# bbf-europower.net
KiCad netlist of a schematic drawn in EAGLE
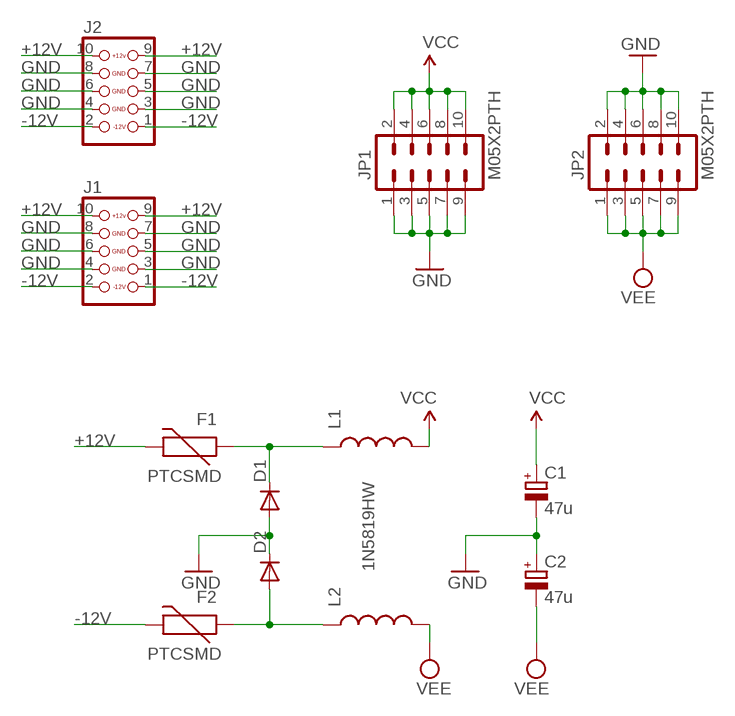
[diagram p0: schematic, sheet 1]

(export (version "E")
  (design (tool "Eeschema 10.0.6"))
  (components
    (comp (ref "C1")
      (value "47u")
      (footprint "eagle-import:E2-5")
      (libsource (lib "eagle-import") (part "CPOL-EUE2-5"))
    )
    (comp (ref "C2")
      (value "47u")
      (footprint "eagle-import:E2-5")
      (libsource (lib "eagle-import") (part "CPOL-EUE2-5"))
    )
    (comp (ref "D1")
      (value "1N5819HW")
      (footprint "eagle-import:SOD123")
      (libsource (lib "eagle-import") (part "DIODE-SOD123"))
    )
    (comp (ref "D2")
      (value "1N5819HW")
      (footprint "eagle-import:SOD123")
      (libsource (lib "eagle-import") (part "DIODE-SOD123"))
    )
    (comp (ref "F1")
      (value "PTCSMD")
      (footprint "eagle-import:PTC-1206")
      (libsource (lib "eagle-import") (part "PTCSMD"))
    )
    (comp (ref "F2")
      (value "PTCSMD")
      (footprint "eagle-import:PTC-1206")
      (libsource (lib "eagle-import") (part "PTCSMD"))
    )
    (comp (ref "J1")
      (value "CON_HEADER_2X05-PTH")
      (footprint "eagle-import:M2X5")
      (libsource (lib "eagle-import") (part "CON_HEADER_2X05-PTH"))
    )
    (comp (ref "J2")
      (value "CON_HEADER_2X05-PTH")
      (footprint "eagle-import:M2X5")
      (libsource (lib "eagle-import") (part "CON_HEADER_2X05-PTH"))
    )
    (comp (ref "JP1")
      (value "M05X2PTH")
      (footprint "eagle-import:AVR_ICSP")
      (libsource (lib "eagle-import") (part "M05X2PTH"))
    )
    (comp (ref "JP2")
      (value "M05X2PTH")
      (footprint "eagle-import:AVR_ICSP")
      (libsource (lib "eagle-import") (part "M05X2PTH"))
    )
    (comp (ref "L1")
      (value "INDUCTOR0603")
      (footprint "eagle-import:0603")
      (libsource (lib "eagle-import") (part "INDUCTOR0603"))
    )
    (comp (ref "L2")
      (value "INDUCTOR0603")
      (footprint "eagle-import:0603")
      (libsource (lib "eagle-import") (part "INDUCTOR0603"))
    )
  )
  (nets
    (net (code "1") (name "/+12V") (class "Default")
      (node (ref "F1") (pin "2") (pinfunction "2_2") (pintype "bidirectional"))
      (node (ref "J1") (pin "10") (pinfunction "10_10") (pintype "passive"))
      (node (ref "J1") (pin "9") (pinfunction "9_9") (pintype "passive"))
      (node (ref "J2") (pin "10") (pinfunction "10_10") (pintype "passive"))
      (node (ref "J2") (pin "9") (pinfunction "9_9") (pintype "passive"))
    )
    (net (code "2") (name "/-12V") (class "Default")
      (node (ref "F2") (pin "2") (pinfunction "2_2") (pintype "bidirectional"))
      (node (ref "J1") (pin "1") (pinfunction "1_1") (pintype "passive"))
      (node (ref "J1") (pin "2") (pinfunction "2_2") (pintype "passive"))
      (node (ref "J2") (pin "1") (pinfunction "1_1") (pintype "passive"))
      (node (ref "J2") (pin "2") (pinfunction "2_2") (pintype "passive"))
    )
    (net (code "3") (name "GND") (class "Default")
      (node (ref "C1") (pin "-") (pinfunction "-_-") (pintype "passive"))
      (node (ref "C2") (pin "+") (pinfunction "+_+") (pintype "passive"))
      (node (ref "D1") (pin "A") (pinfunction "A_A") (pintype "passive"))
      (node (ref "D2") (pin "C") (pinfunction "C_C") (pintype "passive"))
      (node (ref "J1") (pin "3") (pinfunction "3_3") (pintype "passive"))
      (node (ref "J1") (pin "4") (pinfunction "4_4") (pintype "passive"))
      (node (ref "J1") (pin "5") (pinfunction "5_5") (pintype "passive"))
      (node (ref "J1") (pin "6") (pinfunction "6_6") (pintype "passive"))
      (node (ref "J1") (pin "7") (pinfunction "7_7") (pintype "passive"))
      (node (ref "J1") (pin "8") (pinfunction "8_8") (pintype "passive"))
      (node (ref "J2") (pin "3") (pinfunction "3_3") (pintype "passive"))
      (node (ref "J2") (pin "4") (pinfunction "4_4") (pintype "passive"))
      (node (ref "J2") (pin "5") (pinfunction "5_5") (pintype "passive"))
      (node (ref "J2") (pin "6") (pinfunction "6_6") (pintype "passive"))
      (node (ref "J2") (pin "7") (pinfunction "7_7") (pintype "passive"))
      (node (ref "J2") (pin "8") (pinfunction "8_8") (pintype "passive"))
      (node (ref "JP1") (pin "1") (pinfunction "1_1") (pintype "passive"))
      (node (ref "JP1") (pin "3") (pinfunction "3_3") (pintype "passive"))
      (node (ref "JP1") (pin "5") (pinfunction "5_5") (pintype "passive"))
      (node (ref "JP1") (pin "7") (pinfunction "7_7") (pintype "passive"))
      (node (ref "JP1") (pin "9") (pinfunction "9_9") (pintype "passive"))
      (node (ref "JP2") (pin "10") (pinfunction "10_10") (pintype "passive"))
      (node (ref "JP2") (pin "2") (pinfunction "2_2") (pintype "passive"))
      (node (ref "JP2") (pin "4") (pinfunction "4_4") (pintype "passive"))
      (node (ref "JP2") (pin "6") (pinfunction "6_6") (pintype "passive"))
      (node (ref "JP2") (pin "8") (pinfunction "8_8") (pintype "passive"))
    )
    (net (code "4") (name "Net-(D1-PadC)") (class "Default")
      (node (ref "D1") (pin "C") (pinfunction "C_C") (pintype "passive"))
      (node (ref "F1") (pin "1") (pinfunction "1_1") (pintype "bidirectional"))
      (node (ref "L1") (pin "1") (pinfunction "1_1") (pintype "passive"))
    )
    (net (code "5") (name "Net-(D2-PadA)") (class "Default")
      (node (ref "D2") (pin "A") (pinfunction "A_A") (pintype "passive"))
      (node (ref "F2") (pin "1") (pinfunction "1_1") (pintype "bidirectional"))
      (node (ref "L2") (pin "1") (pinfunction "1_1") (pintype "passive"))
    )
    (net (code "6") (name "VCC") (class "Default")
      (node (ref "C1") (pin "+") (pinfunction "+_+") (pintype "passive"))
      (node (ref "JP1") (pin "10") (pinfunction "10_10") (pintype "passive"))
      (node (ref "JP1") (pin "2") (pinfunction "2_2") (pintype "passive"))
      (node (ref "JP1") (pin "4") (pinfunction "4_4") (pintype "passive"))
      (node (ref "JP1") (pin "6") (pinfunction "6_6") (pintype "passive"))
      (node (ref "JP1") (pin "8") (pinfunction "8_8") (pintype "passive"))
      (node (ref "L1") (pin "2") (pinfunction "2_2") (pintype "passive"))
    )
    (net (code "7") (name "VEE") (class "Default")
      (node (ref "C2") (pin "-") (pinfunction "-_-") (pintype "passive"))
      (node (ref "JP2") (pin "1") (pinfunction "1_1") (pintype "passive"))
      (node (ref "JP2") (pin "3") (pinfunction "3_3") (pintype "passive"))
      (node (ref "JP2") (pin "5") (pinfunction "5_5") (pintype "passive"))
      (node (ref "JP2") (pin "7") (pinfunction "7_7") (pintype "passive"))
      (node (ref "JP2") (pin "9") (pinfunction "9_9") (pintype "passive"))
      (node (ref "L2") (pin "2") (pinfunction "2_2") (pintype "passive"))
    )
  )
)
